# KickerBoard5.net
KiCad netlist of a schematic drawn in EAGLE
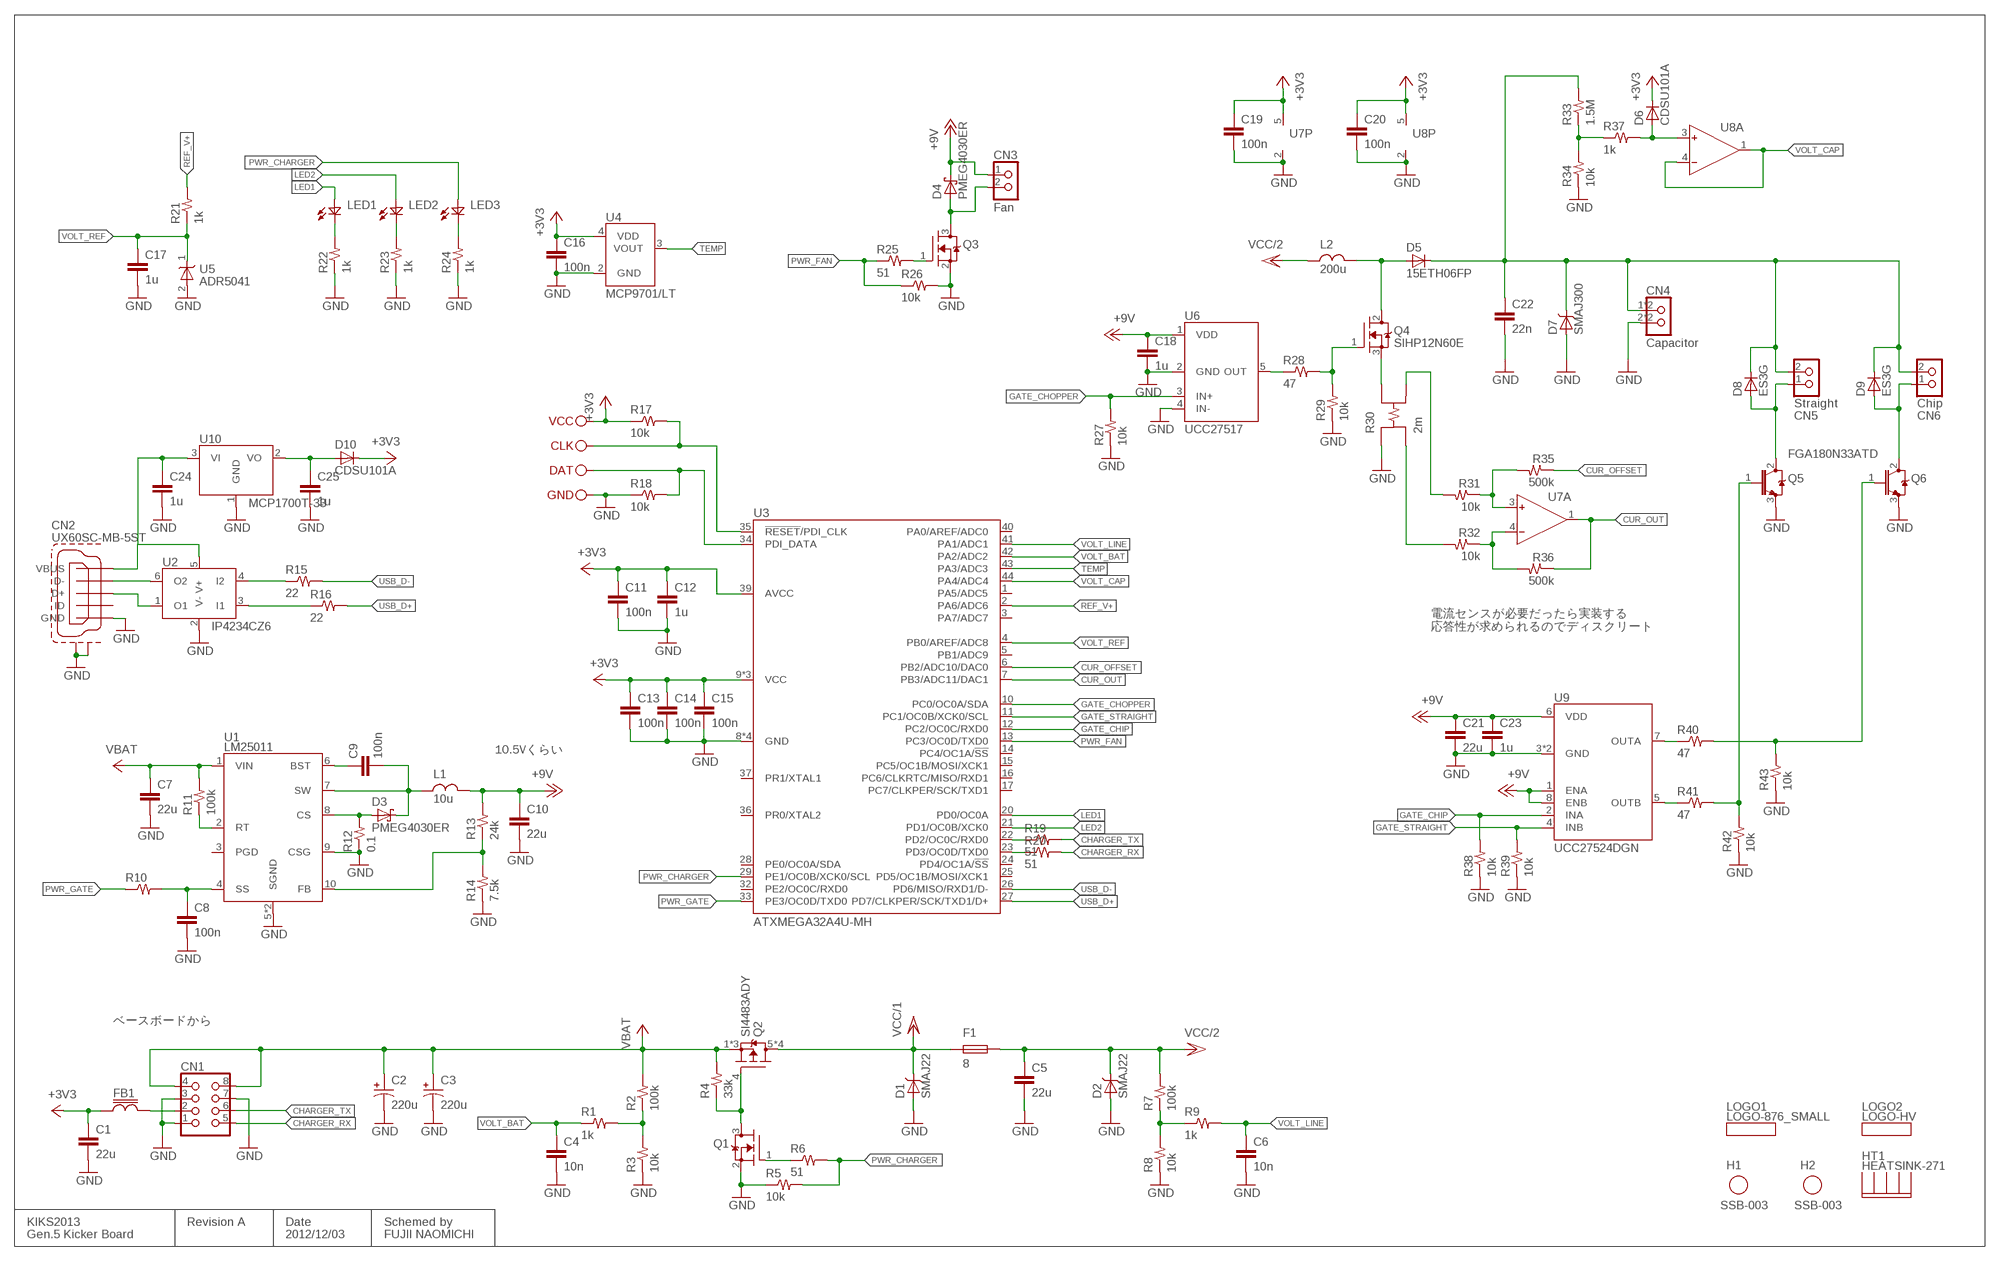
[diagram p0: schematic, sheet 1]

(export (version "E")
  (design (tool "Eeschema 10.0.6"))
  (components
    (comp (ref "C1")
      (value "22u")
      (footprint "eagle-import:2012")
      (libsource (lib "eagle-import") (part "C2012"))
    )
    (comp (ref "C2")
      (value "220u")
      (footprint "eagle-import:E3.5-8")
      (libsource (lib "eagle-import") (part "CPOL3.5-8"))
    )
    (comp (ref "C3")
      (value "220u")
      (footprint "eagle-import:E3.5-8")
      (libsource (lib "eagle-import") (part "CPOL3.5-8"))
    )
    (comp (ref "C4")
      (value "10n")
      (footprint "eagle-import:1005")
      (libsource (lib "eagle-import") (part "C1005"))
    )
    (comp (ref "C5")
      (value "22u")
      (footprint "eagle-import:3225")
      (libsource (lib "eagle-import") (part "C3225"))
    )
    (comp (ref "C6")
      (value "10n")
      (footprint "eagle-import:1005")
      (libsource (lib "eagle-import") (part "C1005"))
    )
    (comp (ref "C7")
      (value "22u")
      (footprint "eagle-import:3216")
      (libsource (lib "eagle-import") (part "C3216"))
    )
    (comp (ref "C8")
      (value "100n")
      (footprint "eagle-import:1005")
      (libsource (lib "eagle-import") (part "C1005"))
    )
    (comp (ref "C9")
      (value "100n")
      (footprint "eagle-import:1608")
      (libsource (lib "eagle-import") (part "C1608"))
    )
    (comp (ref "C10")
      (value "22u")
      (footprint "eagle-import:3216")
      (libsource (lib "eagle-import") (part "C3216"))
    )
    (comp (ref "C11")
      (value "100n")
      (footprint "eagle-import:1005")
      (libsource (lib "eagle-import") (part "C1005"))
    )
    (comp (ref "C12")
      (value "1u")
      (footprint "eagle-import:1608")
      (libsource (lib "eagle-import") (part "C1608"))
    )
    (comp (ref "C13")
      (value "100n")
      (footprint "eagle-import:1005")
      (libsource (lib "eagle-import") (part "C1005"))
    )
    (comp (ref "C14")
      (value "100n")
      (footprint "eagle-import:1005")
      (libsource (lib "eagle-import") (part "C1005"))
    )
    (comp (ref "C15")
      (value "100n")
      (footprint "eagle-import:1005")
      (libsource (lib "eagle-import") (part "C1005"))
    )
    (comp (ref "C16")
      (value "100n")
      (footprint "eagle-import:1005")
      (libsource (lib "eagle-import") (part "C1005"))
    )
    (comp (ref "C17")
      (value "1u")
      (footprint "eagle-import:1005")
      (libsource (lib "eagle-import") (part "C1005"))
    )
    (comp (ref "C18")
      (value "1u")
      (footprint "eagle-import:1608")
      (libsource (lib "eagle-import") (part "C1608"))
    )
    (comp (ref "C19")
      (value "100n")
      (footprint "eagle-import:1005")
      (libsource (lib "eagle-import") (part "C1005"))
    )
    (comp (ref "C20")
      (value "100n")
      (footprint "eagle-import:1005")
      (libsource (lib "eagle-import") (part "C1005"))
    )
    (comp (ref "C21")
      (value "22u")
      (footprint "eagle-import:3216")
      (libsource (lib "eagle-import") (part "C3216"))
    )
    (comp (ref "C22")
      (value "22n")
      (footprint "eagle-import:3216")
      (libsource (lib "eagle-import") (part "C3216"))
    )
    (comp (ref "C23")
      (value "1u")
      (footprint "eagle-import:1608")
      (libsource (lib "eagle-import") (part "C1608"))
    )
    (comp (ref "C24")
      (value "1u")
      (footprint "eagle-import:1005")
      (libsource (lib "eagle-import") (part "C1005"))
    )
    (comp (ref "C25")
      (value "1u")
      (footprint "eagle-import:1005")
      (libsource (lib "eagle-import") (part "C1005"))
    )
    (comp (ref "CN1")
      (value "43045-0800")
      (footprint "eagle-import:43045-0800")
      (libsource (lib "eagle-import") (part "43045-0800"))
    )
    (comp (ref "CN2")
      (value "UX60SC-MB-5ST")
      (footprint "eagle-import:UX60SC-MB-5ST")
      (libsource (lib "eagle-import") (part "UX60SC-MB-5ST"))
    )
    (comp (ref "CN3")
      (value "Fan")
      (footprint "eagle-import:PIN1X2")
      (libsource (lib "eagle-import") (part "PIN1X2"))
    )
    (comp (ref "CN4")
      (value "Capacitor")
      (footprint "eagle-import:TERMINAL2P-V-SCLEWLESS")
      (libsource (lib "eagle-import") (part "TERMINAL2P-V-SL"))
    )
    (comp (ref "CN5")
      (value "Straight")
      (footprint "eagle-import:5569-02A2")
      (libsource (lib "eagle-import") (part "5569-02A2"))
    )
    (comp (ref "CN6")
      (value "Chip")
      (footprint "eagle-import:5569-02A2")
      (libsource (lib "eagle-import") (part "5569-02A2"))
    )
    (comp (ref "D1")
      (value "SMAJ22")
      (footprint "eagle-import:DO-214AC")
      (libsource (lib "eagle-import") (part "ZENER-DO-214AC"))
    )
    (comp (ref "D2")
      (value "SMAJ22")
      (footprint "eagle-import:DO-214AC")
      (libsource (lib "eagle-import") (part "ZENER-DO-214AC"))
    )
    (comp (ref "D3")
      (value "PMEG4030ER")
      (footprint "eagle-import:SOD123W")
      (libsource (lib "eagle-import") (part "SBD-SDO123W"))
    )
    (comp (ref "D4")
      (value "PMEG4030ER")
      (footprint "eagle-import:SOD123W")
      (libsource (lib "eagle-import") (part "SBD-SDO123W"))
    )
    (comp (ref "D5")
      (value "15ETH06FP")
      (footprint "eagle-import:TO-220F-2")
      (libsource (lib "eagle-import") (part "DIODE-TO-220F"))
    )
    (comp (ref "D6")
      (value "CDSU101A")
      (footprint "eagle-import:1608")
      (libsource (lib "eagle-import") (part "DIODE-1608"))
    )
    (comp (ref "D7")
      (value "SMAJ300")
      (footprint "eagle-import:DO-214AC")
      (libsource (lib "eagle-import") (part "ZENER-DO-214AC"))
    )
    (comp (ref "D8")
      (value "ES3G")
      (footprint "eagle-import:DO-214AB")
      (libsource (lib "eagle-import") (part "DIODE-DO-214AB"))
    )
    (comp (ref "D9")
      (value "ES3G")
      (footprint "eagle-import:DO-214AB")
      (libsource (lib "eagle-import") (part "DIODE-DO-214AB"))
    )
    (comp (ref "D10")
      (value "CDSU101A")
      (footprint "eagle-import:1608")
      (libsource (lib "eagle-import") (part "DIODE-1608"))
    )
    (comp (ref "F1")
      (value "8")
      (footprint "eagle-import:3216")
      (libsource (lib "eagle-import") (part "F3216"))
    )
    (comp (ref "FB1")
      (value "FB1608")
      (footprint "eagle-import:1608")
      (libsource (lib "eagle-import") (part "FB1608"))
    )
    (comp (ref "H1")
      (value "SSB-003")
      (footprint "eagle-import:SBB-003")
      (libsource (lib "eagle-import") (part "SSB-003"))
    )
    (comp (ref "H2")
      (value "SSB-003")
      (footprint "eagle-import:SBB-003")
      (libsource (lib "eagle-import") (part "SSB-003"))
    )
    (comp (ref "HT1")
      (value "HEATSINK-271")
      (footprint "eagle-import:271-AB")
      (libsource (lib "eagle-import") (part "HEATSINK-271"))
    )
    (comp (ref "L1")
      (value "10u")
      (footprint "eagle-import:L4040")
      (libsource (lib "eagle-import") (part "L40"))
    )
    (comp (ref "L2")
      (value "200u")
      (footprint "eagle-import:COIL-V")
      (libsource (lib "eagle-import") (part "COIL-V"))
    )
    (comp (ref "LED1")
      (value "LED1608")
      (footprint "eagle-import:1608")
      (libsource (lib "eagle-import") (part "LED1608"))
    )
    (comp (ref "LED2")
      (value "LED1608")
      (footprint "eagle-import:1608")
      (libsource (lib "eagle-import") (part "LED1608"))
    )
    (comp (ref "LED3")
      (value "LED1608")
      (footprint "eagle-import:1608")
      (libsource (lib "eagle-import") (part "LED1608"))
    )
    (comp (ref "LOGO1")
      (value "LOGO-876_SMALL")
      (footprint "eagle-import:LOGO-876_SMALL")
      (libsource (lib "eagle-import") (part "LOGO-876_SMALL"))
    )
    (comp (ref "LOGO2")
      (value "LOGO-HV")
      (footprint "eagle-import:LOGO-HIGHVOLTAGE")
      (libsource (lib "eagle-import") (part "LOGO-HV"))
    )
    (comp (ref "P1")
      (value "VCC")
      (footprint "eagle-import:PAD")
      (libsource (lib "eagle-import") (part "PAD"))
    )
    (comp (ref "P2")
      (value "CLK")
      (footprint "eagle-import:PAD")
      (libsource (lib "eagle-import") (part "PAD"))
    )
    (comp (ref "P3")
      (value "DAT")
      (footprint "eagle-import:PAD")
      (libsource (lib "eagle-import") (part "PAD"))
    )
    (comp (ref "P4")
      (value "GND")
      (footprint "eagle-import:PAD")
      (libsource (lib "eagle-import") (part "PAD"))
    )
    (comp (ref "Q1")
      (value "MOS-N-SOT23")
      (footprint "eagle-import:SOT23-3")
      (libsource (lib "eagle-import") (part "MOS-N-SOT23"))
    )
    (comp (ref "Q2")
      (value "SI4483ADY")
      (footprint "eagle-import:SOP8")
      (libsource (lib "eagle-import") (part "MOS-P-SOP8"))
    )
    (comp (ref "Q3")
      (value "MOS-N-SOT23")
      (footprint "eagle-import:SOT23-3")
      (libsource (lib "eagle-import") (part "MOS-N-SOT23"))
    )
    (comp (ref "Q4")
      (value "SIHP12N60E")
      (footprint "eagle-import:TO-220F")
      (libsource (lib "eagle-import") (part "MOS-N-TO-220F"))
    )
    (comp (ref "Q5")
      (value "FGA180N33ATD")
      (footprint "eagle-import:TO-3P")
      (libsource (lib "eagle-import") (part "IGBT-NTO-3P"))
    )
    (comp (ref "Q6")
      (value "FGA180N33ATD")
      (footprint "eagle-import:TO-3P")
      (libsource (lib "eagle-import") (part "IGBT-NTO-3P"))
    )
    (comp (ref "R1")
      (value "1k")
      (footprint "eagle-import:1005")
      (libsource (lib "eagle-import") (part "R1005"))
    )
    (comp (ref "R2")
      (value "100k")
      (footprint "eagle-import:1608")
      (libsource (lib "eagle-import") (part "R1608"))
    )
    (comp (ref "R3")
      (value "10k")
      (footprint "eagle-import:1608")
      (libsource (lib "eagle-import") (part "R1608"))
    )
    (comp (ref "R4")
      (value "33k")
      (footprint "eagle-import:1005")
      (libsource (lib "eagle-import") (part "R1005"))
    )
    (comp (ref "R5")
      (value "10k")
      (footprint "eagle-import:1005")
      (libsource (lib "eagle-import") (part "R1005"))
    )
    (comp (ref "R6")
      (value "51")
      (footprint "eagle-import:1005")
      (libsource (lib "eagle-import") (part "R1005"))
    )
    (comp (ref "R7")
      (value "100k")
      (footprint "eagle-import:1608")
      (libsource (lib "eagle-import") (part "R1608"))
    )
    (comp (ref "R8")
      (value "10k")
      (footprint "eagle-import:1608")
      (libsource (lib "eagle-import") (part "R1608"))
    )
    (comp (ref "R9")
      (value "1k")
      (footprint "eagle-import:1005")
      (libsource (lib "eagle-import") (part "R1005"))
    )
    (comp (ref "R10")
      (value "R1005")
      (footprint "eagle-import:1005")
      (libsource (lib "eagle-import") (part "R1005"))
    )
    (comp (ref "R11")
      (value "100k")
      (footprint "eagle-import:1005")
      (libsource (lib "eagle-import") (part "R1005"))
    )
    (comp (ref "R12")
      (value "0.1")
      (footprint "eagle-import:2012")
      (libsource (lib "eagle-import") (part "R2012"))
    )
    (comp (ref "R13")
      (value "24k")
      (footprint "eagle-import:1608")
      (libsource (lib "eagle-import") (part "R1608"))
    )
    (comp (ref "R14")
      (value "7.5k")
      (footprint "eagle-import:1608")
      (libsource (lib "eagle-import") (part "R1608"))
    )
    (comp (ref "R15")
      (value "22")
      (footprint "eagle-import:1005")
      (libsource (lib "eagle-import") (part "R1005"))
    )
    (comp (ref "R16")
      (value "22")
      (footprint "eagle-import:1005")
      (libsource (lib "eagle-import") (part "R1005"))
    )
    (comp (ref "R17")
      (value "10k")
      (footprint "eagle-import:1005")
      (libsource (lib "eagle-import") (part "R1005"))
    )
    (comp (ref "R18")
      (value "10k")
      (footprint "eagle-import:1005")
      (libsource (lib "eagle-import") (part "R1005"))
    )
    (comp (ref "R19")
      (value "51")
      (footprint "eagle-import:1005")
      (libsource (lib "eagle-import") (part "R1005"))
    )
    (comp (ref "R20")
      (value "51")
      (footprint "eagle-import:1005")
      (libsource (lib "eagle-import") (part "R1005"))
    )
    (comp (ref "R21")
      (value "1k")
      (footprint "eagle-import:1005")
      (libsource (lib "eagle-import") (part "R1005"))
    )
    (comp (ref "R22")
      (value "1k")
      (footprint "eagle-import:1005")
      (libsource (lib "eagle-import") (part "R1005"))
    )
    (comp (ref "R23")
      (value "1k")
      (footprint "eagle-import:1005")
      (libsource (lib "eagle-import") (part "R1005"))
    )
    (comp (ref "R24")
      (value "1k")
      (footprint "eagle-import:1005")
      (libsource (lib "eagle-import") (part "R1005"))
    )
    (comp (ref "R25")
      (value "51")
      (footprint "eagle-import:1005")
      (libsource (lib "eagle-import") (part "R1005"))
    )
    (comp (ref "R26")
      (value "10k")
      (footprint "eagle-import:1005")
      (libsource (lib "eagle-import") (part "R1005"))
    )
    (comp (ref "R27")
      (value "10k")
      (footprint "eagle-import:1005")
      (libsource (lib "eagle-import") (part "R1005"))
    )
    (comp (ref "R28")
      (value "47")
      (footprint "eagle-import:3216")
      (libsource (lib "eagle-import") (part "R3216"))
    )
    (comp (ref "R29")
      (value "10k")
      (footprint "eagle-import:1005")
      (libsource (lib "eagle-import") (part "R1005"))
    )
    (comp (ref "R30")
      (value "2m")
      (footprint "eagle-import:FC4L")
      (libsource (lib "eagle-import") (part "FC4L"))
    )
    (comp (ref "R31")
      (value "10k")
      (footprint "eagle-import:1608")
      (libsource (lib "eagle-import") (part "R1608"))
    )
    (comp (ref "R32")
      (value "10k")
      (footprint "eagle-import:1608")
      (libsource (lib "eagle-import") (part "R1608"))
    )
    (comp (ref "R33")
      (value "1.5M")
      (footprint "eagle-import:1608")
      (libsource (lib "eagle-import") (part "R1608"))
    )
    (comp (ref "R34")
      (value "10k")
      (footprint "eagle-import:1608")
      (libsource (lib "eagle-import") (part "R1608"))
    )
    (comp (ref "R35")
      (value "500k")
      (footprint "eagle-import:1608")
      (libsource (lib "eagle-import") (part "R1608"))
    )
    (comp (ref "R36")
      (value "500k")
      (footprint "eagle-import:1608")
      (libsource (lib "eagle-import") (part "R1608"))
    )
    (comp (ref "R37")
      (value "1k")
      (footprint "eagle-import:1005")
      (libsource (lib "eagle-import") (part "R1005"))
    )
    (comp (ref "R38")
      (value "10k")
      (footprint "eagle-import:1005")
      (libsource (lib "eagle-import") (part "R1005"))
    )
    (comp (ref "R39")
      (value "10k")
      (footprint "eagle-import:1005")
      (libsource (lib "eagle-import") (part "R1005"))
    )
    (comp (ref "R40")
      (value "47")
      (footprint "eagle-import:3216")
      (libsource (lib "eagle-import") (part "R3216"))
    )
    (comp (ref "R41")
      (value "47")
      (footprint "eagle-import:3216")
      (libsource (lib "eagle-import") (part "R3216"))
    )
    (comp (ref "R42")
      (value "10k")
      (footprint "eagle-import:1005")
      (libsource (lib "eagle-import") (part "R1005"))
    )
    (comp (ref "R43")
      (value "10k")
      (footprint "eagle-import:1005")
      (libsource (lib "eagle-import") (part "R1005"))
    )
    (comp (ref "U1")
      (value "LM25011")
      (footprint "eagle-import:MSOP10-PAD")
      (libsource (lib "eagle-import") (part "LM25011"))
    )
    (comp (ref "U2")
      (value "IP4234CZ6")
      (footprint "eagle-import:SOT23-6")
      (libsource (lib "eagle-import") (part "TPD2S017"))
    )
    (comp (ref "U3")
      (value "ATXMEGA32A4U-MH")
      (footprint "eagle-import:QFN44-0.5")
      (libsource (lib "eagle-import") (part "ATXMEGAA4U-MH32"))
    )
    (comp (ref "U4")
      (value "MCP9701/LT")
      (footprint "eagle-import:SC70-6")
      (libsource (lib "eagle-import") (part "MCP970/LT1"))
    )
    (comp (ref "U5")
      (value "ADR5041")
      (footprint "eagle-import:SC70-3")
      (libsource (lib "eagle-import") (part "ADR5041"))
    )
    (comp (ref "U6")
      (value "UCC27517")
      (footprint "eagle-import:SOT23-5")
      (libsource (lib "eagle-import") (part "UCC27517"))
    )
    (comp (ref "U7")
      (value "SINGLE-OPAMP-ISO-SOT23")
      (footprint "eagle-import:SOT23-5")
      (libsource (lib "eagle-import") (part "SINGLE-OPAMP-ISO-SOT23"))
    )
    (comp (ref "U8")
      (value "SINGLE-OPAMP-ISO-SOT23")
      (footprint "eagle-import:SOT23-5")
      (libsource (lib "eagle-import") (part "SINGLE-OPAMP-ISO-SOT23"))
    )
    (comp (ref "U9")
      (value "UCC27524DGN")
      (footprint "eagle-import:MSOP8-PAD")
      (libsource (lib "eagle-import") (part "UCC27524DGN"))
    )
    (comp (ref "U10")
      (value "MCP1700T-33")
      (footprint "eagle-import:SOT23-3")
      (libsource (lib "eagle-import") (part "MCP1700T-33"))
    )
  )
  (nets
    (net (code "1") (name "+3V3") (class "Default")
      (node (ref "C1") (pin "1") (pinfunction "1_1") (pintype "passive"))
      (node (ref "C11") (pin "1") (pinfunction "1_1") (pintype "passive"))
      (node (ref "C12") (pin "1") (pinfunction "1_1") (pintype "passive"))
      (node (ref "C13") (pin "1") (pinfunction "1_1") (pintype "passive"))
      (node (ref "C14") (pin "1") (pinfunction "1_1") (pintype "passive"))
      (node (ref "C15") (pin "1") (pinfunction "1_1") (pintype "passive"))
      (node (ref "C16") (pin "1") (pinfunction "1_1") (pintype "passive"))
      (node (ref "C19") (pin "1") (pinfunction "1_1") (pintype "passive"))
      (node (ref "C20") (pin "1") (pinfunction "1_1") (pintype "passive"))
      (node (ref "D10") (pin "K") (pinfunction "K_K") (pintype "passive"))
      (node (ref "D6") (pin "K") (pinfunction "K_K") (pintype "passive"))
      (node (ref "FB1") (pin "1") (pinfunction "1_1") (pintype "passive"))
      (node (ref "P1") (pin "1") (pinfunction "P$1_1") (pintype "passive"))
      (node (ref "R17") (pin "1") (pinfunction "1_1") (pintype "passive"))
      (node (ref "U3") (pin "19") (pinfunction "VCC_19") (pintype "bidirectional"))
      (node (ref "U3") (pin "31") (pinfunction "VCC_31") (pintype "bidirectional"))
      (node (ref "U3") (pin "39") (pinfunction "AVCC_39") (pintype "bidirectional"))
      (node (ref "U3") (pin "9") (pinfunction "VCC_9") (pintype "bidirectional"))
      (node (ref "U4") (pin "4") (pinfunction "VDD_4") (pintype "bidirectional"))
      (node (ref "U7") (pin "5") (pinfunction "V+_5") (pintype "input"))
      (node (ref "U8") (pin "5") (pinfunction "V+_5") (pintype "input"))
    )
    (net (code "2") (name "+9V") (class "Default")
      (node (ref "C10") (pin "1") (pinfunction "1_1") (pintype "passive"))
      (node (ref "C18") (pin "1") (pinfunction "1_1") (pintype "passive"))
      (node (ref "C21") (pin "1") (pinfunction "1_1") (pintype "passive"))
      (node (ref "C23") (pin "1") (pinfunction "1_1") (pintype "passive"))
      (node (ref "CN3") (pin "1") (pinfunction "1_1") (pintype "passive"))
      (node (ref "D4") (pin "K") (pinfunction "K_K") (pintype "passive"))
      (node (ref "L1") (pin "2") (pinfunction "2_2") (pintype "passive"))
      (node (ref "R13") (pin "2") (pinfunction "2_2") (pintype "passive"))
      (node (ref "U6") (pin "1") (pinfunction "VDD_1") (pintype "bidirectional"))
      (node (ref "U9") (pin "1") (pinfunction "ENA_1") (pintype "bidirectional"))
      (node (ref "U9") (pin "6") (pinfunction "VDD_6") (pintype "bidirectional"))
      (node (ref "U9") (pin "8") (pinfunction "ENB_8") (pintype "bidirectional"))
    )
    (net (code "3") (name "CHARGER_RX") (class "Default")
      (node (ref "CN1") (pin "5") (pinfunction "5_5") (pintype "passive"))
      (node (ref "R20") (pin "2") (pinfunction "2_2") (pintype "passive"))
    )
    (net (code "4") (name "CHARGER_TX") (class "Default")
      (node (ref "CN1") (pin "6") (pinfunction "6_6") (pintype "passive"))
      (node (ref "R19") (pin "2") (pinfunction "2_2") (pintype "passive"))
    )
    (net (code "5") (name "CUR_OFFSET") (class "Default")
      (node (ref "R35") (pin "1") (pinfunction "1_1") (pintype "passive"))
      (node (ref "U3") (pin "6") (pinfunction "PB2/ADC10/DAC0_6") (pintype "bidirectional"))
    )
    (net (code "6") (name "CUR_OUT") (class "Default")
      (node (ref "R36") (pin "1") (pinfunction "1_1") (pintype "passive"))
      (node (ref "U3") (pin "7") (pinfunction "PB3/ADC11/DAC1_7") (pintype "bidirectional"))
      (node (ref "U7") (pin "1") (pinfunction "OUT_1") (pintype "output"))
    )
    (net (code "7") (name "GATE_CHIP") (class "Default")
      (node (ref "R38") (pin "2") (pinfunction "2_2") (pintype "passive"))
      (node (ref "U3") (pin "12") (pinfunction "PC2/OC0C/RXD0_12") (pintype "bidirectional"))
      (node (ref "U9") (pin "2") (pinfunction "INA_2") (pintype "bidirectional"))
    )
    (net (code "8") (name "GATE_CHOPPER") (class "Default")
      (node (ref "R27") (pin "2") (pinfunction "2_2") (pintype "passive"))
      (node (ref "U3") (pin "10") (pinfunction "PC0/OC0A/SDA_10") (pintype "bidirectional"))
      (node (ref "U6") (pin "3") (pinfunction "IN+_3") (pintype "bidirectional"))
    )
    (net (code "9") (name "GATE_STRAIGHT") (class "Default")
      (node (ref "R39") (pin "2") (pinfunction "2_2") (pintype "passive"))
      (node (ref "U3") (pin "11") (pinfunction "PC1/OC0B/XCK0/SCL_11") (pintype "bidirectional"))
      (node (ref "U9") (pin "4") (pinfunction "INB_4") (pintype "bidirectional"))
    )
    (net (code "10") (name "GND") (class "Default")
      (node (ref "C1") (pin "2") (pinfunction "2_2") (pintype "passive"))
      (node (ref "C10") (pin "2") (pinfunction "2_2") (pintype "passive"))
      (node (ref "C11") (pin "2") (pinfunction "2_2") (pintype "passive"))
      (node (ref "C12") (pin "2") (pinfunction "2_2") (pintype "passive"))
      (node (ref "C13") (pin "2") (pinfunction "2_2") (pintype "passive"))
      (node (ref "C14") (pin "2") (pinfunction "2_2") (pintype "passive"))
      (node (ref "C15") (pin "2") (pinfunction "2_2") (pintype "passive"))
      (node (ref "C16") (pin "2") (pinfunction "2_2") (pintype "passive"))
      (node (ref "C17") (pin "2") (pinfunction "2_2") (pintype "passive"))
      (node (ref "C18") (pin "2") (pinfunction "2_2") (pintype "passive"))
      (node (ref "C19") (pin "2") (pinfunction "2_2") (pintype "passive"))
      (node (ref "C2") (pin "N") (pinfunction "N_N") (pintype "passive"))
      (node (ref "C20") (pin "2") (pinfunction "2_2") (pintype "passive"))
      (node (ref "C21") (pin "2") (pinfunction "2_2") (pintype "passive"))
      (node (ref "C22") (pin "2") (pinfunction "2_2") (pintype "passive"))
      (node (ref "C23") (pin "2") (pinfunction "2_2") (pintype "passive"))
      (node (ref "C24") (pin "2") (pinfunction "2_2") (pintype "passive"))
      (node (ref "C25") (pin "2") (pinfunction "2_2") (pintype "passive"))
      (node (ref "C3") (pin "N") (pinfunction "N_N") (pintype "passive"))
      (node (ref "C4") (pin "2") (pinfunction "2_2") (pintype "passive"))
      (node (ref "C5") (pin "2") (pinfunction "2_2") (pintype "passive"))
      (node (ref "C6") (pin "2") (pinfunction "2_2") (pintype "passive"))
      (node (ref "C7") (pin "2") (pinfunction "2_2") (pintype "passive"))
      (node (ref "C8") (pin "2") (pinfunction "2_2") (pintype "passive"))
      (node (ref "CN1") (pin "1") (pinfunction "1_1") (pintype "passive"))
      (node (ref "CN1") (pin "3") (pinfunction "3_3") (pintype "passive"))
      (node (ref "CN1") (pin "7") (pinfunction "7_7") (pintype "passive"))
      (node (ref "CN2") (pin "5") (pinfunction "GND_5") (pintype "passive"))
      (node (ref "CN2") (pin "S1") (pinfunction "S1_S1") (pintype "passive"))
      (node (ref "CN2") (pin "S2") (pinfunction "S2_S2") (pintype "passive"))
      (node (ref "CN4") (pin "2") (pinfunction "2_2") (pintype "passive"))
      (node (ref "CN4") (pin "2B") (pinfunction "2_2B") (pintype "passive"))
      (node (ref "D1") (pin "A") (pinfunction "A_A") (pintype "passive"))
      (node (ref "D2") (pin "A") (pinfunction "A_A") (pintype "passive"))
      (node (ref "D7") (pin "A") (pinfunction "A_A") (pintype "passive"))
      (node (ref "P4") (pin "1") (pinfunction "P$1_1") (pintype "passive"))
      (node (ref "Q1") (pin "2") (pinfunction "S_2") (pintype "passive"))
      (node (ref "Q3") (pin "2") (pinfunction "S_2") (pintype "passive"))
      (node (ref "Q5") (pin "3") (pinfunction "E_3") (pintype "passive"))
      (node (ref "Q6") (pin "3") (pinfunction "E_3") (pintype "passive"))
      (node (ref "R12") (pin "1") (pinfunction "1_1") (pintype "passive"))
      (node (ref "R14") (pin "1") (pinfunction "1_1") (pintype "passive"))
      (node (ref "R18") (pin "1") (pinfunction "1_1") (pintype "passive"))
      (node (ref "R22") (pin "1") (pinfunction "1_1") (pintype "passive"))
      (node (ref "R23") (pin "1") (pinfunction "1_1") (pintype "passive"))
      (node (ref "R24") (pin "1") (pinfunction "1_1") (pintype "passive"))
      (node (ref "R26") (pin "2") (pinfunction "2_2") (pintype "passive"))
      (node (ref "R27") (pin "1") (pinfunction "1_1") (pintype "passive"))
      (node (ref "R29") (pin "1") (pinfunction "1_1") (pintype "passive"))
      (node (ref "R3") (pin "1") (pinfunction "1_1") (pintype "passive"))
      (node (ref "R30") (pin "V1") (pinfunction "V1_V1") (pintype "passive"))
      (node (ref "R34") (pin "1") (pinfunction "1_1") (pintype "passive"))
      (node (ref "R38") (pin "1") (pinfunction "1_1") (pintype "passive"))
      (node (ref "R39") (pin "1") (pinfunction "1_1") (pintype "passive"))
      (node (ref "R42") (pin "1") (pinfunction "1_1") (pintype "passive"))
      (node (ref "R43") (pin "1") (pinfunction "1_1") (pintype "passive"))
      (node (ref "R5") (pin "1") (pinfunction "1_1") (pintype "passive"))
      (node (ref "R8") (pin "1") (pinfunction "1_1") (pintype "passive"))
      (node (ref "U1") (pin "5") (pinfunction "SGND_5") (pintype "bidirectional"))
      (node (ref "U1") (pin "9") (pinfunction "CSG_9") (pintype "bidirectional"))
      (node (ref "U1") (pin "PAD") (pinfunction "SGND_PAD") (pintype "bidirectional"))
      (node (ref "U10") (pin "1") (pinfunction "GND_1") (pintype "bidirectional"))
      (node (ref "U2") (pin "2") (pinfunction "V-_2") (pintype "bidirectional"))
      (node (ref "U3") (pin "18") (pinfunction "GND_18") (pintype "bidirectional"))
      (node (ref "U3") (pin "30") (pinfunction "GND_30") (pintype "bidirectional"))
      (node (ref "U3") (pin "38") (pinfunction "GND_38") (pintype "bidirectional"))
      (node (ref "U3") (pin "8") (pinfunction "GND_8") (pintype "bidirectional"))
      (node (ref "U4") (pin "2") (pinfunction "GND_2") (pintype "bidirectional"))
      (node (ref "U5") (pin "2") (pinfunction "A_2") (pintype "passive"))
      (node (ref "U6") (pin "2") (pinfunction "GND_2") (pintype "bidirectional"))
      (node (ref "U6") (pin "4") (pinfunction "IN-_4") (pintype "bidirectional"))
      (node (ref "U7") (pin "2") (pinfunction "V-_2") (pintype "input"))
      (node (ref "U8") (pin "2") (pinfunction "V-_2") (pintype "input"))
      (node (ref "U9") (pin "3") (pinfunction "GND_3") (pintype "bidirectional"))
      (node (ref "U9") (pin "PAD") (pinfunction "GND_PAD") (pintype "bidirectional"))
    )
    (net (code "11") (name "LED1") (class "Default")
      (node (ref "LED1") (pin "A") (pinfunction "A_A") (pintype "passive"))
      (node (ref "U3") (pin "20") (pinfunction "PD0/OC0A_20") (pintype "bidirectional"))
    )
    (net (code "12") (name "LED2") (class "Default")
      (node (ref "LED2") (pin "A") (pinfunction "A_A") (pintype "passive"))
      (node (ref "U3") (pin "21") (pinfunction "PD1/OC0B/XCK0_21") (pintype "bidirectional"))
    )
    (net (code "13") (name "Net-(CN1-Pad2)") (class "Default")
      (node (ref "CN1") (pin "2") (pinfunction "2_2") (pintype "passive"))
      (node (ref "FB1") (pin "2") (pinfunction "2_2") (pintype "passive"))
    )
    (net (code "14") (name "Net-(CN2-D+)") (class "Default")
      (node (ref "CN2") (pin "3") (pinfunction "D+_3") (pintype "passive"))
      (node (ref "U2") (pin "1") (pinfunction "O1_1") (pintype "bidirectional"))
    )
    (net (code "15") (name "Net-(CN2-D-)") (class "Default")
      (node (ref "CN2") (pin "2") (pinfunction "D-_2") (pintype "passive"))
      (node (ref "U2") (pin "6") (pinfunction "O2_6") (pintype "bidirectional"))
    )
    (net (code "16") (name "Net-(CN2-VBUS)") (class "Default")
      (node (ref "C24") (pin "1") (pinfunction "1_1") (pintype "passive"))
      (node (ref "CN2") (pin "1") (pinfunction "VBUS_1") (pintype "passive"))
      (node (ref "U10") (pin "3") (pinfunction "VI_3") (pintype "bidirectional"))
      (node (ref "U2") (pin "5") (pinfunction "V+_5") (pintype "bidirectional"))
    )
    (net (code "17") (name "Net-(D5-A)") (class "Default")
      (node (ref "D5") (pin "3") (pinfunction "A_3") (pintype "passive"))
      (node (ref "L2") (pin "2") (pinfunction "2_2") (pintype "passive"))
      (node (ref "Q4") (pin "2") (pinfunction "D_2") (pintype "passive"))
    )
    (net (code "18") (name "Net-(D5-K)") (class "Default")
      (node (ref "C22") (pin "1") (pinfunction "1_1") (pintype "passive"))
      (node (ref "CN4") (pin "1") (pinfunction "1_1") (pintype "passive"))
      (node (ref "CN4") (pin "1B") (pinfunction "1_1B") (pintype "passive"))
      (node (ref "CN5") (pin "2") (pinfunction "2_2") (pintype "passive"))
      (node (ref "CN6") (pin "2") (pinfunction "2_2") (pintype "passive"))
      (node (ref "D5") (pin "1") (pinfunction "K_1") (pintype "passive"))
      (node (ref "D7") (pin "K") (pinfunction "K_K") (pintype "passive"))
      (node (ref "D8") (pin "K") (pinfunction "K_K") (pintype "passive"))
      (node (ref "D9") (pin "K") (pinfunction "K_K") (pintype "passive"))
      (node (ref "R33") (pin "2") (pinfunction "2_2") (pintype "passive"))
    )
    (net (code "19") (name "Net-(LED1-PadK)") (class "Default")
      (node (ref "LED1") (pin "K") (pinfunction "K_K") (pintype "passive"))
      (node (ref "R22") (pin "2") (pinfunction "2_2") (pintype "passive"))
    )
    (net (code "20") (name "Net-(LED2-PadK)") (class "Default")
      (node (ref "LED2") (pin "K") (pinfunction "K_K") (pintype "passive"))
      (node (ref "R23") (pin "2") (pinfunction "2_2") (pintype "passive"))
    )
    (net (code "21") (name "Net-(LED3-PadK)") (class "Default")
      (node (ref "LED3") (pin "K") (pinfunction "K_K") (pintype "passive"))
      (node (ref "R24") (pin "2") (pinfunction "2_2") (pintype "passive"))
    )
    (net (code "22") (name "Net-(P2-P$1)") (class "Default")
      (node (ref "P2") (pin "1") (pinfunction "P$1_1") (pintype "passive"))
      (node (ref "R17") (pin "2") (pinfunction "2_2") (pintype "passive"))
      (node (ref "U3") (pin "35") (pinfunction "~{RESET}/PDI_CLK_35") (pintype "bidirectional"))
    )
    (net (code "23") (name "Net-(P3-P$1)") (class "Default")
      (node (ref "P3") (pin "1") (pinfunction "P$1_1") (pintype "passive"))
      (node (ref "R18") (pin "2") (pinfunction "2_2") (pintype "passive"))
      (node (ref "U3") (pin "34") (pinfunction "PDI_DATA_34") (pintype "bidirectional"))
    )
    (net (code "24") (name "Net-(Q1-D)") (class "Default")
      (node (ref "Q1") (pin "3") (pinfunction "D_3") (pintype "passive"))
      (node (ref "Q2") (pin "4") (pinfunction "G_4") (pintype "passive"))
      (node (ref "R4") (pin "1") (pinfunction "1_1") (pintype "passive"))
    )
    (net (code "25") (name "Net-(Q1-G)") (class "Default")
      (node (ref "Q1") (pin "1") (pinfunction "G_1") (pintype "passive"))
      (node (ref "R6") (pin "1") (pinfunction "1_1") (pintype "passive"))
    )
    (net (code "26") (name "Net-(Q3-D)") (class "Default")
      (node (ref "CN3") (pin "2") (pinfunction "2_2") (pintype "passive"))
      (node (ref "D4") (pin "A") (pinfunction "A_A") (pintype "passive"))
      (node (ref "Q3") (pin "3") (pinfunction "D_3") (pintype "passive"))
    )
    (net (code "27") (name "Net-(Q3-G)") (class "Default")
      (node (ref "Q3") (pin "1") (pinfunction "G_1") (pintype "passive"))
      (node (ref "R25") (pin "2") (pinfunction "2_2") (pintype "passive"))
    )
    (net (code "28") (name "Net-(Q4-G)") (class "Default")
      (node (ref "Q4") (pin "1") (pinfunction "G_1") (pintype "passive"))
      (node (ref "R28") (pin "2") (pinfunction "2_2") (pintype "passive"))
      (node (ref "R29") (pin "2") (pinfunction "2_2") (pintype "passive"))
    )
    (net (code "29") (name "Net-(Q4-S)") (class "Default")
      (node (ref "Q4") (pin "3") (pinfunction "S_3") (pintype "passive"))
      (node (ref "R30") (pin "V2") (pinfunction "V2_V2") (pintype "passive"))
    )
    (net (code "30") (name "Net-(Q5-C)") (class "Default")
      (node (ref "CN5") (pin "1") (pinfunction "1_1") (pintype "passive"))
      (node (ref "D8") (pin "A") (pinfunction "A_A") (pintype "passive"))
      (node (ref "Q5") (pin "2") (pinfunction "C_2") (pintype "passive"))
    )
    (net (code "31") (name "Net-(Q5-G)") (class "Default")
      (node (ref "Q5") (pin "1") (pinfunction "G_1") (pintype "passive"))
      (node (ref "R41") (pin "2") (pinfunction "2_2") (pintype "passive"))
      (node (ref "R42") (pin "2") (pinfunction "2_2") (pintype "passive"))
    )
    (net (code "32") (name "Net-(Q6-C)") (class "Default")
      (node (ref "CN6") (pin "1") (pinfunction "1_1") (pintype "passive"))
      (node (ref "D9") (pin "A") (pinfunction "A_A") (pintype "passive"))
      (node (ref "Q6") (pin "2") (pinfunction "C_2") (pintype "passive"))
    )
    (net (code "33") (name "Net-(Q6-G)") (class "Default")
      (node (ref "Q6") (pin "1") (pinfunction "G_1") (pintype "passive"))
      (node (ref "R40") (pin "2") (pinfunction "2_2") (pintype "passive"))
      (node (ref "R43") (pin "2") (pinfunction "2_2") (pintype "passive"))
    )
    (net (code "34") (name "Net-(R1-Pad2)") (class "Default")
      (node (ref "R1") (pin "2") (pinfunction "2_2") (pintype "passive"))
      (node (ref "R2") (pin "1") (pinfunction "1_1") (pintype "passive"))
      (node (ref "R3") (pin "2") (pinfunction "2_2") (pintype "passive"))
    )
    (net (code "35") (name "Net-(R7-Pad1)") (class "Default")
      (node (ref "R7") (pin "1") (pinfunction "1_1") (pintype "passive"))
      (node (ref "R8") (pin "2") (pinfunction "2_2") (pintype "passive"))
      (node (ref "R9") (pin "1") (pinfunction "1_1") (pintype "passive"))
    )
    (net (code "36") (name "Net-(R30-PadI1)") (class "Default")
      (node (ref "R30") (pin "I1") (pinfunction "I1_I1") (pintype "passive"))
      (node (ref "R32") (pin "2") (pinfunction "2_2") (pintype "passive"))
    )
    (net (code "37") (name "Net-(R30-PadI2)") (class "Default")
      (node (ref "R30") (pin "I2") (pinfunction "I2_I2") (pintype "passive"))
      (node (ref "R31") (pin "2") (pinfunction "2_2") (pintype "passive"))
    )
    (net (code "38") (name "Net-(R33-Pad1)") (class "Default")
      (node (ref "R33") (pin "1") (pinfunction "1_1") (pintype "passive"))
      (node (ref "R34") (pin "2") (pinfunction "2_2") (pintype "passive"))
      (node (ref "R37") (pin "1") (pinfunction "1_1") (pintype "passive"))
    )
    (net (code "39") (name "Net-(U1-BST)") (class "Default")
      (node (ref "C9") (pin "1") (pinfunction "1_1") (pintype "passive"))
      (node (ref "U1") (pin "6") (pinfunction "BST_6") (pintype "bidirectional"))
    )
    (net (code "40") (name "Net-(U1-CS)") (class "Default")
      (node (ref "D3") (pin "A") (pinfunction "A_A") (pintype "passive"))
      (node (ref "R12") (pin "2") (pinfunction "2_2") (pintype "passive"))
      (node (ref "U1") (pin "8") (pinfunction "CS_8") (pintype "bidirectional"))
    )
    (net (code "41") (name "Net-(U1-FB)") (class "Default")
      (node (ref "R13") (pin "1") (pinfunction "1_1") (pintype "passive"))
      (node (ref "R14") (pin "2") (pinfunction "2_2") (pintype "passive"))
      (node (ref "U1") (pin "10") (pinfunction "FB_10") (pintype "bidirectional"))
    )
    (net (code "42") (name "Net-(U1-RT)") (class "Default")
      (node (ref "R11") (pin "1") (pinfunction "1_1") (pintype "passive"))
      (node (ref "U1") (pin "2") (pinfunction "RT_2") (pintype "bidirectional"))
    )
    (net (code "43") (name "Net-(U1-SS)") (class "Default")
      (node (ref "C8") (pin "1") (pinfunction "1_1") (pintype "passive"))
      (node (ref "R10") (pin "2") (pinfunction "2_2") (pintype "passive"))
      (node (ref "U1") (pin "4") (pinfunction "SS_4") (pintype "bidirectional"))
    )
    (net (code "44") (name "Net-(U1-SW)") (class "Default")
      (node (ref "C9") (pin "2") (pinfunction "2_2") (pintype "passive"))
      (node (ref "D3") (pin "K") (pinfunction "K_K") (pintype "passive"))
      (node (ref "L1") (pin "1") (pinfunction "1_1") (pintype "passive"))
      (node (ref "U1") (pin "7") (pinfunction "SW_7") (pintype "bidirectional"))
    )
    (net (code "45") (name "Net-(U2-I1)") (class "Default")
      (node (ref "R16") (pin "1") (pinfunction "1_1") (pintype "passive"))
      (node (ref "U2") (pin "3") (pinfunction "I1_3") (pintype "bidirectional"))
    )
    (net (code "46") (name "Net-(U2-I2)") (class "Default")
      (node (ref "R15") (pin "1") (pinfunction "1_1") (pintype "passive"))
      (node (ref "U2") (pin "4") (pinfunction "I2_4") (pintype "bidirectional"))
    )
    (net (code "47") (name "Net-(U3-PD2{slash}OC0C{slash}RXD0)") (class "Default")
      (node (ref "R19") (pin "1") (pinfunction "1_1") (pintype "passive"))
      (node (ref "U3") (pin "22") (pinfunction "PD2/OC0C/RXD0_22") (pintype "bidirectional"))
    )
    (net (code "48") (name "Net-(U3-PD3{slash}OC0D{slash}TXD0)") (class "Default")
      (node (ref "R20") (pin "1") (pinfunction "1_1") (pintype "passive"))
      (node (ref "U3") (pin "23") (pinfunction "PD3/OC0D/TXD0_23") (pintype "bidirectional"))
    )
    (net (code "49") (name "Net-(U6-OUT)") (class "Default")
      (node (ref "R28") (pin "1") (pinfunction "1_1") (pintype "passive"))
      (node (ref "U6") (pin "5") (pinfunction "OUT_5") (pintype "bidirectional"))
    )
    (net (code "50") (name "Net-(U7A-IN+)") (class "Default")
      (node (ref "R31") (pin "1") (pinfunction "1_1") (pintype "passive"))
      (node (ref "R35") (pin "2") (pinfunction "2_2") (pintype "passive"))
      (node (ref "U7") (pin "3") (pinfunction "IN+_3") (pintype "input"))
    )
    (net (code "51") (name "Net-(U7A-IN-)") (class "Default")
      (node (ref "R32") (pin "1") (pinfunction "1_1") (pintype "passive"))
      (node (ref "R36") (pin "2") (pinfunction "2_2") (pintype "passive"))
      (node (ref "U7") (pin "4") (pinfunction "IN-_4") (pintype "input"))
    )
    (net (code "52") (name "Net-(U8A-IN+)") (class "Default")
      (node (ref "D6") (pin "A") (pinfunction "A_A") (pintype "passive"))
      (node (ref "R37") (pin "2") (pinfunction "2_2") (pintype "passive"))
      (node (ref "U8") (pin "3") (pinfunction "IN+_3") (pintype "input"))
    )
    (net (code "53") (name "Net-(U9-OUTA)") (class "Default")
      (node (ref "R40") (pin "1") (pinfunction "1_1") (pintype "passive"))
      (node (ref "U9") (pin "7") (pinfunction "OUTA_7") (pintype "bidirectional"))
    )
    (net (code "54") (name "Net-(U9-OUTB)") (class "Default")
      (node (ref "R41") (pin "1") (pinfunction "1_1") (pintype "passive"))
      (node (ref "U9") (pin "5") (pinfunction "OUTB_5") (pintype "bidirectional"))
    )
    (net (code "55") (name "Net-(U10-VO)") (class "Default")
      (node (ref "C25") (pin "1") (pinfunction "1_1") (pintype "passive"))
      (node (ref "D10") (pin "A") (pinfunction "A_A") (pintype "passive"))
      (node (ref "U10") (pin "2") (pinfunction "VO_2") (pintype "bidirectional"))
    )
    (net (code "56") (name "PWR_CHARGER") (class "Default")
      (node (ref "LED3") (pin "A") (pinfunction "A_A") (pintype "passive"))
      (node (ref "R5") (pin "2") (pinfunction "2_2") (pintype "passive"))
      (node (ref "R6") (pin "2") (pinfunction "2_2") (pintype "passive"))
      (node (ref "U3") (pin "29") (pinfunction "PE1/OC0B/XCK0/SCL_29") (pintype "bidirectional"))
    )
    (net (code "57") (name "PWR_FAN") (class "Default")
      (node (ref "R25") (pin "1") (pinfunction "1_1") (pintype "passive"))
      (node (ref "R26") (pin "1") (pinfunction "1_1") (pintype "passive"))
      (node (ref "U3") (pin "13") (pinfunction "PC3/OC0D/TXD0_13") (pintype "bidirectional"))
    )
    (net (code "58") (name "PWR_GATE") (class "Default")
      (node (ref "R10") (pin "1") (pinfunction "1_1") (pintype "passive"))
      (node (ref "U3") (pin "33") (pinfunction "PE3/OC0D/TXD0_33") (pintype "bidirectional"))
    )
    (net (code "59") (name "REF_V+") (class "Default")
      (node (ref "R21") (pin "2") (pinfunction "2_2") (pintype "passive"))
      (node (ref "U3") (pin "2") (pinfunction "PA6/ADC6_2") (pintype "bidirectional"))
    )
    (net (code "60") (name "TEMP") (class "Default")
      (node (ref "U3") (pin "43") (pinfunction "PA3/ADC3_43") (pintype "bidirectional"))
      (node (ref "U4") (pin "3") (pinfunction "VOUT_3") (pintype "bidirectional"))
    )
    (net (code "61") (name "USB_D+") (class "Default")
      (node (ref "R16") (pin "2") (pinfunction "2_2") (pintype "passive"))
      (node (ref "U3") (pin "27") (pinfunction "PD7/CLKPER/SCK/TXD1/D+_27") (pintype "bidirectional"))
    )
    (net (code "62") (name "USB_D-") (class "Default")
      (node (ref "R15") (pin "2") (pinfunction "2_2") (pintype "passive"))
      (node (ref "U3") (pin "26") (pinfunction "PD6/MISO/RXD1/D-_26") (pintype "bidirectional"))
    )
    (net (code "63") (name "VBAT") (class "Default")
      (node (ref "C2") (pin "P") (pinfunction "P_P") (pintype "passive"))
      (node (ref "C3") (pin "P") (pinfunction "P_P") (pintype "passive"))
      (node (ref "C7") (pin "1") (pinfunction "1_1") (pintype "passive"))
      (node (ref "CN1") (pin "4") (pinfunction "4_4") (pintype "passive"))
      (node (ref "CN1") (pin "8") (pinfunction "8_8") (pintype "passive"))
      (node (ref "Q2") (pin "1") (pinfunction "S_1") (pintype "passive"))
      (node (ref "Q2") (pin "2") (pinfunction "S_2") (pintype "passive"))
      (node (ref "Q2") (pin "3") (pinfunction "S_3") (pintype "passive"))
      (node (ref "R11") (pin "2") (pinfunction "2_2") (pintype "passive"))
      (node (ref "R2") (pin "2") (pinfunction "2_2") (pintype "passive"))
      (node (ref "R4") (pin "2") (pinfunction "2_2") (pintype "passive"))
      (node (ref "U1") (pin "1") (pinfunction "VIN_1") (pintype "bidirectional"))
    )
    (net (code "64") (name "VCC{slash}1") (class "Default")
      (node (ref "D1") (pin "K") (pinfunction "K_K") (pintype "passive"))
      (node (ref "F1") (pin "1") (pinfunction "1_1") (pintype "passive"))
      (node (ref "Q2") (pin "5") (pinfunction "D_5") (pintype "passive"))
      (node (ref "Q2") (pin "6") (pinfunction "D_6") (pintype "passive"))
      (node (ref "Q2") (pin "7") (pinfunction "D_7") (pintype "passive"))
      (node (ref "Q2") (pin "8") (pinfunction "D_8") (pintype "passive"))
    )
    (net (code "65") (name "VCC{slash}2") (class "Default")
      (node (ref "C5") (pin "1") (pinfunction "1_1") (pintype "passive"))
      (node (ref "D2") (pin "K") (pinfunction "K_K") (pintype "passive"))
      (node (ref "F1") (pin "2") (pinfunction "2_2") (pintype "passive"))
      (node (ref "L2") (pin "1") (pinfunction "1_1") (pintype "passive"))
      (node (ref "R7") (pin "2") (pinfunction "2_2") (pintype "passive"))
    )
    (net (code "66") (name "VOLT_BAT") (class "Default")
      (node (ref "C4") (pin "1") (pinfunction "1_1") (pintype "passive"))
      (node (ref "R1") (pin "1") (pinfunction "1_1") (pintype "passive"))
      (node (ref "U3") (pin "42") (pinfunction "PA2/ADC2_42") (pintype "bidirectional"))
    )
    (net (code "67") (name "VOLT_CAP") (class "Default")
      (node (ref "U3") (pin "44") (pinfunction "PA4/ADC4_44") (pintype "bidirectional"))
      (node (ref "U8") (pin "1") (pinfunction "OUT_1") (pintype "output"))
      (node (ref "U8") (pin "4") (pinfunction "IN-_4") (pintype "input"))
    )
    (net (code "68") (name "VOLT_LINE") (class "Default")
      (node (ref "C6") (pin "1") (pinfunction "1_1") (pintype "passive"))
      (node (ref "R9") (pin "2") (pinfunction "2_2") (pintype "passive"))
      (node (ref "U3") (pin "41") (pinfunction "PA1/ADC1_41") (pintype "bidirectional"))
    )
    (net (code "69") (name "VOLT_REF") (class "Default")
      (node (ref "C17") (pin "1") (pinfunction "1_1") (pintype "passive"))
      (node (ref "R21") (pin "1") (pinfunction "1_1") (pintype "passive"))
      (node (ref "U3") (pin "4") (pinfunction "PB0/AREF/ADC8_4") (pintype "bidirectional"))
      (node (ref "U5") (pin "1") (pinfunction "K_1") (pintype "passive"))
    )
    (net (code "70") (name "unconnected-(CN2-ID-Pad4)") (class "Default")
      (node (ref "CN2") (pin "4") (pinfunction "ID_4") (pintype "passive"))
    )
    (net (code "71") (name "unconnected-(U1-PGD-Pad3)") (class "Default")
      (node (ref "U1") (pin "3") (pinfunction "PGD_3") (pintype "bidirectional"))
    )
    (net (code "72") (name "unconnected-(U3-PA0{slash}AREF{slash}ADC0-Pad40)") (class "Default")
      (node (ref "U3") (pin "40") (pinfunction "PA0/AREF/ADC0_40") (pintype "bidirectional"))
    )
    (net (code "73") (name "unconnected-(U3-PA5{slash}ADC5-Pad1)") (class "Default")
      (node (ref "U3") (pin "1") (pinfunction "PA5/ADC5_1") (pintype "bidirectional"))
    )
    (net (code "74") (name "unconnected-(U3-PA7{slash}ADC7-Pad3)") (class "Default")
      (node (ref "U3") (pin "3") (pinfunction "PA7/ADC7_3") (pintype "bidirectional"))
    )
    (net (code "75") (name "unconnected-(U3-PB1{slash}ADC9-Pad5)") (class "Default")
      (node (ref "U3") (pin "5") (pinfunction "PB1/ADC9_5") (pintype "bidirectional"))
    )
    (net (code "76") (name "unconnected-(U3-PC4{slash}OC1A{slash}~{SS}-Pad14)") (class "Default")
      (node (ref "U3") (pin "14") (pinfunction "PC4/OC1A/~{SS}_14") (pintype "bidirectional"))
    )
    (net (code "77") (name "unconnected-(U3-PC5{slash}OC1B{slash}MOSI{slash}XCK1-Pad15)") (class "Default")
      (node (ref "U3") (pin "15") (pinfunction "PC5/OC1B/MOSI/XCK1_15") (pintype "bidirectional"))
    )
    (net (code "78") (name "unconnected-(U3-PC6{slash}CLKRTC{slash}MISO{slash}RXD1-Pad16)") (class "Default")
      (node (ref "U3") (pin "16") (pinfunction "PC6/CLKRTC/MISO/RXD1_16") (pintype "bidirectional"))
    )
    (net (code "79") (name "unconnected-(U3-PC7{slash}CLKPER{slash}SCK{slash}TXD1-Pad17)") (class "Default")
      (node (ref "U3") (pin "17") (pinfunction "PC7/CLKPER/SCK/TXD1_17") (pintype "bidirectional"))
    )
    (net (code "80") (name "unconnected-(U3-PD4{slash}OC1A{slash}~{SS}-Pad24)") (class "Default")
      (node (ref "U3") (pin "24") (pinfunction "PD4/OC1A/~{SS}_24") (pintype "bidirectional"))
    )
    (net (code "81") (name "unconnected-(U3-PD5{slash}OC1B{slash}MOSI{slash}XCK1-Pad25)") (class "Default")
      (node (ref "U3") (pin "25") (pinfunction "PD5/OC1B/MOSI/XCK1_25") (pintype "bidirectional"))
    )
    (net (code "82") (name "unconnected-(U3-PE0{slash}OC0A{slash}SDA-Pad28)") (class "Default")
      (node (ref "U3") (pin "28") (pinfunction "PE0/OC0A/SDA_28") (pintype "bidirectional"))
    )
    (net (code "83") (name "unconnected-(U3-PE2{slash}OC0C{slash}RXD0-Pad32)") (class "Default")
      (node (ref "U3") (pin "32") (pinfunction "PE2/OC0C/RXD0_32") (pintype "bidirectional"))
    )
    (net (code "84") (name "unconnected-(U3-PR0{slash}XTAL2-Pad36)") (class "Default")
      (node (ref "U3") (pin "36") (pinfunction "PR0/XTAL2_36") (pintype "bidirectional"))
    )
    (net (code "85") (name "unconnected-(U3-PR1{slash}XTAL1-Pad37)") (class "Default")
      (node (ref "U3") (pin "37") (pinfunction "PR1/XTAL1_37") (pintype "bidirectional"))
    )
  )
)
